# power.net
KiCad netlist of a schematic drawn in Altium Designer
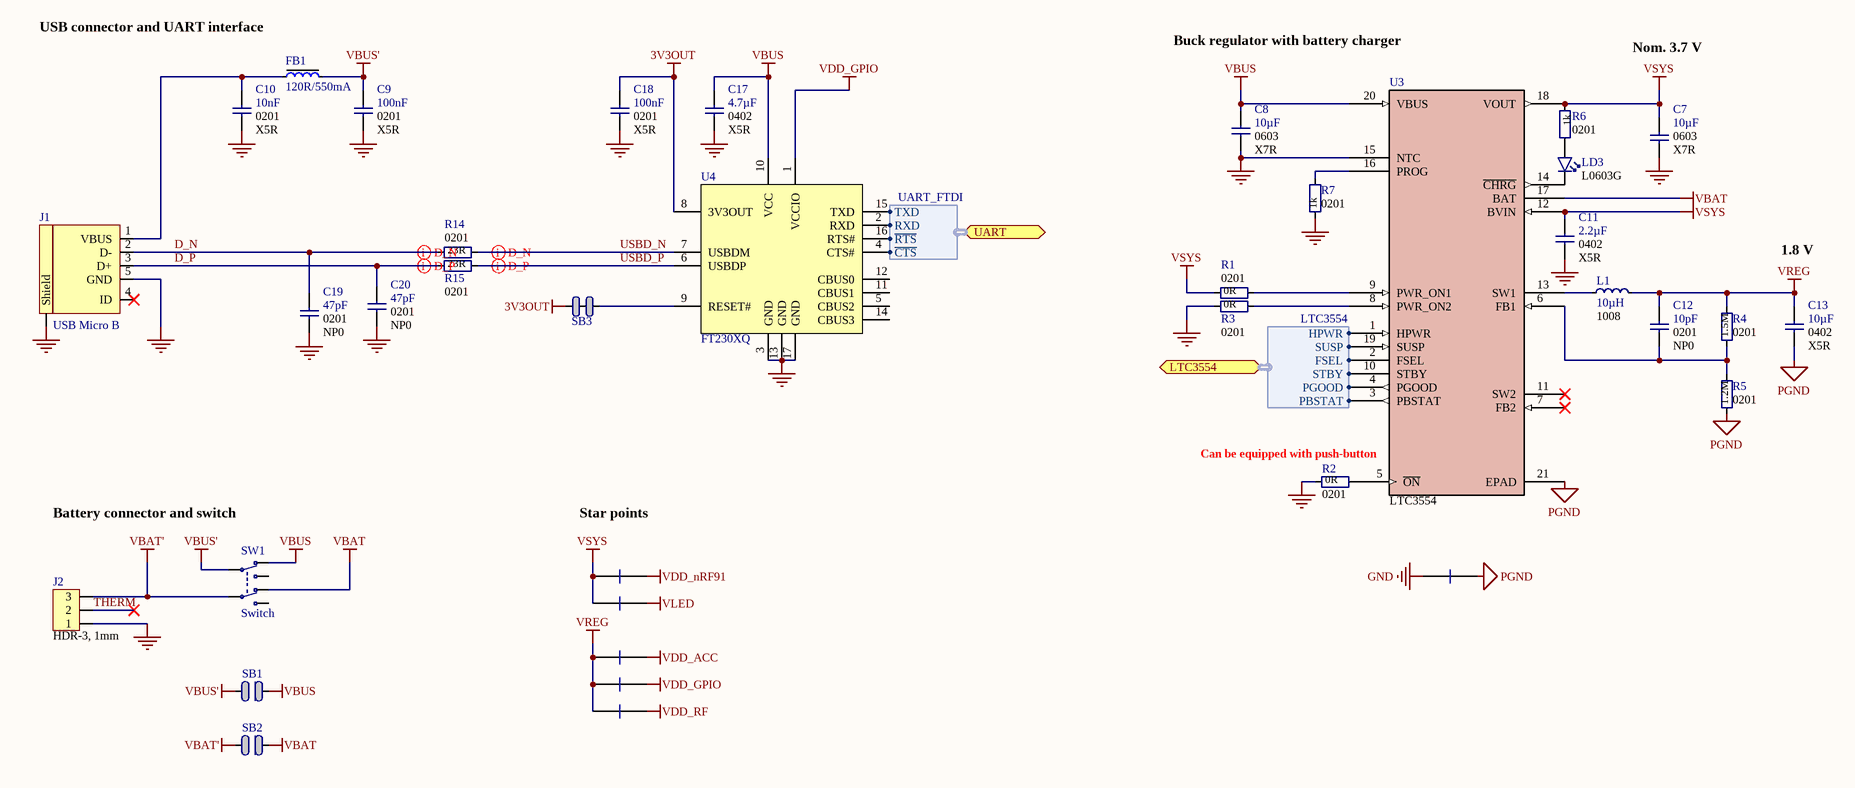
[diagram p0: _power.SchDoc]

(export (version "E")
  (design (tool "Eeschema 10.0.6"))
  (components
    (comp (ref "C7")
      (value "10µF")
      (footprint "CAPC1608X06L")
      (description "Capacitor, X7R, ±10%")
      (fields
        (field (name "FOOTPRINT DOC") "0603")
        (field (name "TEMPCOEFF") "X7R")
        (field (name "PUBLISHER") "Nordic Semiconductor")
      )
      (libsource (lib "_components") (part "CAP{colon}0603"))
    )
    (comp (ref "C8")
      (value "10µF")
      (footprint "CAPC1608X06L")
      (description "Capacitor, X7R, ±10%")
      (fields
        (field (name "FOOTPRINT DOC") "0603")
        (field (name "TEMPCOEFF") "X7R")
        (field (name "PUBLISHER") "Nordic Semiconductor")
      )
      (libsource (lib "_components") (part "CAP{colon}0603"))
    )
    (comp (ref "C9")
      (value "100nF")
      (footprint "CAPC0603X03L_C")
      (description "Capacitor, X5R, ±10%, 10V")
      (fields
        (field (name "FOOTPRINT DOC") "0201")
        (field (name "TEMPCOEFF") "X5R")
        (field (name "PUBLISHER") "Nordic Semiconductor")
      )
      (libsource (lib "_components") (part "CAP{colon}0201"))
    )
    (comp (ref "C10")
      (value "10nF")
      (footprint "CAPC0603X03L_C")
      (description "Capacitor, X5R, ±10%, 10V")
      (fields
        (field (name "FOOTPRINT DOC") "0201")
        (field (name "TEMPCOEFF") "X5R")
        (field (name "PUBLISHER") "Nordic Semiconductor")
      )
      (libsource (lib "_components") (part "CAP{colon}0201"))
    )
    (comp (ref "C11")
      (value "2.2µF")
      (footprint "CAPC1005X04L")
      (description "Capacitor, X5R, ±10%, 16V")
      (fields
        (field (name "FOOTPRINT DOC") "0402")
        (field (name "TEMPCOEFF") "X5R")
        (field (name "PUBLISHER") "Nordic Semiconductor")
      )
      (libsource (lib "_components") (part "CAP{colon}0402"))
    )
    (comp (ref "C12")
      (value "10pF")
      (footprint "CAPC0603X03L_C")
      (description "Capacitor, NP0")
      (fields
        (field (name "FOOTPRINT DOC") "0201")
        (field (name "TEMPCOEFF") "NP0")
        (field (name "PUBLISHER") "Nordic Semiconductor")
      )
      (libsource (lib "_components") (part "CAP{colon}0201"))
    )
    (comp (ref "C13")
      (value "10µF")
      (footprint "CAPC1005X04L")
      (description "Capacitor, X5R, ±20%")
      (fields
        (field (name "FOOTPRINT DOC") "0402")
        (field (name "TEMPCOEFF") "X5R")
        (field (name "PUBLISHER") "Nordic Semiconductor")
      )
      (libsource (lib "_components") (part "CAP{colon}0402"))
    )
    (comp (ref "C17")
      (value "4.7µF")
      (footprint "CAPC1005X04L")
      (description "Capacitor, X5R, ±10%, 16V")
      (fields
        (field (name "FOOTPRINT DOC") "0402")
        (field (name "TEMPCOEFF") "X5R")
        (field (name "PUBLISHER") "Nordic Semiconductor")
      )
      (libsource (lib "_components") (part "CAP{colon}0402"))
    )
    (comp (ref "C18")
      (value "100nF")
      (footprint "CAPC0603X03L_C")
      (description "Capacitor, X5R, ±10%, 10V")
      (fields
        (field (name "FOOTPRINT DOC") "0201")
        (field (name "TEMPCOEFF") "X5R")
        (field (name "PUBLISHER") "Nordic Semiconductor")
      )
      (libsource (lib "_components") (part "CAP{colon}0201"))
    )
    (comp (ref "C19")
      (value "47pF")
      (footprint "CAPC0603X03L_C")
      (description "Capacitor, NP0")
      (fields
        (field (name "FOOTPRINT DOC") "0201")
        (field (name "TEMPCOEFF") "NP0")
        (field (name "PUBLISHER") "Nordic Semiconductor")
      )
      (libsource (lib "_components") (part "CAP{colon}0201"))
    )
    (comp (ref "C20")
      (value "47pF")
      (footprint "CAPC0603X03L_C")
      (description "Capacitor, NP0")
      (fields
        (field (name "FOOTPRINT DOC") "0201")
        (field (name "TEMPCOEFF") "NP0")
        (field (name "PUBLISHER") "Nordic Semiconductor")
      )
      (libsource (lib "_components") (part "CAP{colon}0201"))
    )
    (comp (ref "FB1")
      (value "120R/550mA")
      (footprint "INDC1005X04L")
      (description "Ferrite Bead, 120 Ohm @ 100MHz, 500mA, 250 mOhm Max")
      (fields
        (field (name "PART NUMBER") "FB0805-120R@100M-550mA")
        (field (name "MANUFACTURER") "Murata")
        (field (name "PUBLISHER") "Nordic Semiconductor")
      )
      (libsource (lib "_components") (part "FB0402-120R@100M-500mA"))
    )
    (comp (ref "J1")
      (value "USB Micro B")
      (footprint "USB-Micro-B-RA-SMD-PiP")
      (description "MicroUSB-B-SMT")
      (fields
        (field (name "PART NUMBER") "USB-Micro-B-RA-SMD-PiP")
        (field (name "MANUFACTURER") "Amphenol ICC (FCI)")
        (field (name "PUBLISHER") "Nordic Semiconductor")
      )
      (libsource (lib "_components") (part "MiniUSB-AB-SMT"))
    )
    (comp (ref "J2")
      (value "HDR-3, 1mm")
      (footprint "SM03B-SRSS-TB")
      (description "1.0mm pitch connector side entry SMD")
      (fields
        (field (name "PART NUMBER") "SM03B-SRSS-TB")
        (field (name "MANUFACTURER") "JST")
        (field (name "PUBLISHER") "Nordic Semiconductor")
      )
      (libsource (lib "_components") (part "CONN-3"))
    )
    (comp (ref "L1")
      (value "10µH")
      (footprint "IND1008")
      (description "Switching regulator chip inductor, 2-Leads, Body 2.5x2.0x1.1 mm")
      (fields
        (field (name "MANUFACTURER") "Wurth Electronics Inc.")
        (field (name "MANUFACTURER PART NUMBER") "74479787247")
        (field (name "FOOTPRINT DOC") "1008")
        (field (name "PUBLISHER") "Nordic Semiconductor")
      )
      (libsource (lib "_components") (part "IND{colon}1008_REG"))
    )
    (comp (ref "LD3")
      (value "L0603G")
      (footprint "LED_0603_G")
      (description "LED, Green, 0603, 570nm, Vf=1.7V, 2.24..5.6mcd, - 40 to +100°C")
      (fields
        (field (name "PART NUMBER") "LG L29K Smartled Green")
        (field (name "MANUFACTURER") "Osram")
        (field (name "PUBLISHER") "Nordic Semiconductor")
      )
      (libsource (lib "_components") (part "D{colon}LED"))
    )
    (comp (ref "NT1")
      (value "Star point")
      (footprint "Net_tie_GND")
      (libsource (lib "_components") (part "NT{colon}Trace"))
    )
    (comp (ref "NT2")
      (value "Star point")
      (footprint "Net_tie_trace")
      (libsource (lib "_components") (part "NT{colon}Trace"))
    )
    (comp (ref "NT3")
      (value "Star point")
      (footprint "Net_tie_trace")
      (libsource (lib "_components") (part "NT{colon}Trace"))
    )
    (comp (ref "NT4")
      (value "Star point")
      (footprint "Net_tie_trace")
      (libsource (lib "_components") (part "NT{colon}Trace"))
    )
    (comp (ref "NT5")
      (value "Star point")
      (footprint "Net_tie_trace")
      (libsource (lib "_components") (part "NT{colon}Trace"))
    )
    (comp (ref "NT6")
      (value "Star point")
      (footprint "Net_tie_trace")
      (libsource (lib "_components") (part "NT{colon}Trace"))
    )
    (comp (ref "R1")
      (value "0R")
      (footprint "RESC0603X03L_C")
      (fields (field (name "FOOTPRINT DOC") "0201") (field (name "PUBLISHER") "Nordic Semiconductor"))
      (libsource (lib "") (part "RES{colon}0201_2"))
    )
    (comp (ref "R2")
      (value "0R")
      (footprint "RESC0603X03L_C")
      (fields (field (name "FOOTPRINT DOC") "0201") (field (name "PUBLISHER") "Nordic Semiconductor"))
      (libsource (lib "") (part "RES{colon}0201_2"))
    )
    (comp (ref "R3")
      (value "0R")
      (footprint "RESC0603X03L_C")
      (fields (field (name "FOOTPRINT DOC") "0201") (field (name "PUBLISHER") "Nordic Semiconductor"))
      (libsource (lib "") (part "RES{colon}0201_2"))
    )
    (comp (ref "R4")
      (value "1.5M")
      (footprint "RESC0603X03L_C")
      (fields (field (name "FOOTPRINT DOC") "0201") (field (name "PUBLISHER") "Nordic Semiconductor"))
      (libsource (lib "") (part "RES{colon}0201_1"))
    )
    (comp (ref "R5")
      (value "1.2M")
      (footprint "RESC0603X03L_C")
      (fields (field (name "FOOTPRINT DOC") "0201") (field (name "PUBLISHER") "Nordic Semiconductor"))
      (libsource (lib "") (part "RES{colon}0201_1"))
    )
    (comp (ref "R6")
      (value "1k")
      (footprint "RESC0603X03L_C")
      (fields (field (name "FOOTPRINT DOC") "0201") (field (name "PUBLISHER") "Nordic Semiconductor"))
      (libsource (lib "_components") (part "RES{colon}0201"))
    )
    (comp (ref "R7")
      (value "1k")
      (footprint "RESC0603X03L_C")
      (fields (field (name "FOOTPRINT DOC") "0201") (field (name "PUBLISHER") "Nordic Semiconductor"))
      (libsource (lib "") (part "RES{colon}0201_1"))
    )
    (comp (ref "R14")
      (value "23R")
      (footprint "RESC0603X03L_C")
      (fields (field (name "FOOTPRINT DOC") "0201") (field (name "PUBLISHER") "Nordic Semiconductor"))
      (libsource (lib "") (part "RES{colon}0201_2"))
    )
    (comp (ref "R15")
      (value "23R")
      (footprint "RESC0603X03L_C")
      (fields (field (name "FOOTPRINT DOC") "0201") (field (name "PUBLISHER") "Nordic Semiconductor"))
      (libsource (lib "") (part "RES{colon}0201_2"))
    )
    (comp (ref "SB1")
      (value "Solderbridge")
      (footprint "Solderbridge")
      (fields (field (name "PUBLISHER") "Nordic Semiconductor"))
      (libsource (lib "_components") (part "SOLDERBRIDGE"))
    )
    (comp (ref "SB2")
      (value "Solderbridge")
      (footprint "Solderbridge")
      (fields (field (name "PUBLISHER") "Nordic Semiconductor"))
      (libsource (lib "_components") (part "SOLDERBRIDGE"))
    )
    (comp (ref "SB3")
      (value "Solderbridge")
      (footprint "Solderbridge_Shorted")
      (description "Shorted Solderbridge")
      (fields (field (name "PUBLISHER") "Nordic Semiconductor"))
      (libsource (lib "_components") (part "SOLDERBRIDGE_SHORTED"))
    )
    (comp (ref "SW1")
      (value "Switch")
      (footprint "Switch-Slide-RA-J-Lead-DPDT-8.5x3.5mm")
      (description "SMD slide Switch (ON-ON)")
      (fields
        (field (name "PART NUMBER") "Switch-Slide-RA-J-Lead-DPDT-8.5x3.5mm_Copal")
        (field (name "MANUFACTURER") "Copal Electronics Inc")
        (field (name "PUBLISHER") "Nordic Semiconductor")
      )
      (libsource (lib "_components") (part "SW-DPDT"))
    )
    (comp (ref "U3")
      (value "LTC3554")
      (footprint "QFN40P300X300X80_HS-21N")
      (description "IC USB POWER MANAGER 20UTQFN")
      (fields
        (field (name "MANUFACTURER_PART_NUMBER") "LTC3554EUD-3#PBF")
        (field (name "COPYRIGHT") "Nordic Semiconductor")
      )
      (libsource (lib "_components") (part "LTC3554EUD-3#PBF"))
    )
    (comp (ref "U4")
      (value "FT230XQ")
      (footprint "QFN65P400X400X80_HS-17N")
      (description "USB Bridge, USB to UART USB 2.0 UART Interface 16-QFN (4x4)")
      (fields (field (name "MANUFACTURER") "FTDI") (field (name "PUBLISHER") "Nordic Semiconductor"))
      (libsource (lib "_components") (part "FT230X"))
    )
  )
  (nets
    (net (code "3") (name "/D_N") (class "Default")
      (node (ref "C19") (pin "2") (pinfunction "2_2") (pintype "passive"))
      (node (ref "J1") (pin "2") (pinfunction "D-_2") (pintype "passive"))
      (node (ref "R14") (pin "1") (pinfunction "1_1") (pintype "passive"))
    )
    (net (code "4") (name "/D_P") (class "Default")
      (node (ref "C20") (pin "1") (pinfunction "1_1") (pintype "passive"))
      (node (ref "J1") (pin "3") (pinfunction "D+_3") (pintype "passive"))
      (node (ref "R15") (pin "1") (pinfunction "1_1") (pintype "passive"))
    )
    (net (code "5") (name "/FSEL") (class "Default")
      (node (ref "U3") (pin "2") (pinfunction "FSEL_2") (pintype "passive"))
    )
    (net (code "6") (name "/HPWR") (class "Default")
      (node (ref "U3") (pin "1") (pinfunction "HPWR_1") (pintype "input"))
    )
    (net (code "7") (name "/PBSTAT") (class "Default")
      (node (ref "U3") (pin "3") (pinfunction "PBSTAT_3") (pintype "output"))
    )
    (net (code "8") (name "/PGOOD") (class "Default")
      (node (ref "U3") (pin "4") (pinfunction "PGOOD_4") (pintype "output"))
    )
    (net (code "9") (name "/RXD") (class "Default")
      (node (ref "U4") (pin "2") (pinfunction "RXD_2") (pintype "passive"))
    )
    (net (code "10") (name "/STBY") (class "Default")
      (node (ref "U3") (pin "10") (pinfunction "STBY_10") (pintype "passive"))
    )
    (net (code "11") (name "/SUSP") (class "Default")
      (node (ref "U3") (pin "19") (pinfunction "SUSP_19") (pintype "input"))
    )
    (net (code "12") (name "/THERM") (class "Default")
      (node (ref "J2") (pin "2") (pinfunction "2_2") (pintype "passive+no_connect"))
    )
    (net (code "13") (name "/TXD") (class "Default")
      (node (ref "U4") (pin "15") (pinfunction "TXD_15") (pintype "passive"))
    )
    (net (code "14") (name "/USBD_N") (class "Default")
      (node (ref "R14") (pin "2") (pinfunction "2_2") (pintype "passive"))
      (node (ref "U4") (pin "7") (pinfunction "USBDM_7") (pintype "passive"))
    )
    (net (code "15") (name "/USBD_P") (class "Default")
      (node (ref "R15") (pin "2") (pinfunction "2_2") (pintype "passive"))
      (node (ref "U4") (pin "6") (pinfunction "USBDP_6") (pintype "passive"))
    )
    (net (code "18") (name "/~{CTS}") (class "Default")
      (node (ref "U4") (pin "4") (pinfunction "CTS#_4") (pintype "passive"))
    )
    (net (code "19") (name "/~{RTS}") (class "Default")
      (node (ref "U4") (pin "16") (pinfunction "RTS#_16") (pintype "power_in"))
    )
    (net (code "20") (name "3V3OUT") (class "Default")
      (node (ref "C18") (pin "1") (pinfunction "1_1") (pintype "passive"))
      (node (ref "SB3") (pin "2") (pinfunction "1_2") (pintype "passive"))
      (node (ref "U4") (pin "8") (pinfunction "3V3OUT_8") (pintype "passive"))
    )
    (net (code "21") (name "GND") (class "Default")
      (node (ref "C10") (pin "2") (pinfunction "2_2") (pintype "passive"))
      (node (ref "C11") (pin "2") (pinfunction "2_2") (pintype "passive"))
      (node (ref "C17") (pin "2") (pinfunction "2_2") (pintype "passive"))
      (node (ref "C18") (pin "2") (pinfunction "2_2") (pintype "passive"))
      (node (ref "C19") (pin "1") (pinfunction "1_1") (pintype "passive"))
      (node (ref "C20") (pin "2") (pinfunction "2_2") (pintype "passive"))
      (node (ref "C7") (pin "2") (pinfunction "2_2") (pintype "passive"))
      (node (ref "C8") (pin "2") (pinfunction "2_2") (pintype "passive"))
      (node (ref "C9") (pin "2") (pinfunction "2_2") (pintype "passive"))
      (node (ref "J1") (pin "5") (pinfunction "GND_5") (pintype "power_in"))
      (node (ref "J1") (pin "6") (pinfunction "Shield_6") (pintype "power_in"))
      (node (ref "J2") (pin "1") (pinfunction "1_1") (pintype "passive"))
      (node (ref "NT1") (pin "1") (pinfunction "1_1") (pintype "passive"))
      (node (ref "R2") (pin "1") (pinfunction "1_1") (pintype "passive"))
      (node (ref "R3") (pin "1") (pinfunction "1_1") (pintype "passive"))
      (node (ref "R7") (pin "1") (pinfunction "1_1") (pintype "passive"))
      (node (ref "U3") (pin "15") (pinfunction "NTC_15") (pintype "passive"))
      (node (ref "U4") (pin "13") (pinfunction "GND_13") (pintype "power_in"))
      (node (ref "U4") (pin "17") (pinfunction "GND_17") (pintype "power_in"))
      (node (ref "U4") (pin "3") (pinfunction "GND_3") (pintype "passive"))
    )
    (net (code "22") (name "Net-(J1-VBUS)") (class "Default")
      (node (ref "C10") (pin "1") (pinfunction "1_1") (pintype "passive"))
      (node (ref "FB1") (pin "1") (pinfunction "1_1") (pintype "passive"))
      (node (ref "J1") (pin "1") (pinfunction "VBUS_1") (pintype "power_in"))
    )
    (net (code "23") (name "Net-(LD3-A)") (class "Default")
      (node (ref "LD3") (pin "2") (pinfunction "A_2") (pintype "passive"))
      (node (ref "R6") (pin "2") (pinfunction "2_2") (pintype "passive"))
    )
    (net (code "24") (name "Net-(LD3-C)") (class "Default")
      (node (ref "LD3") (pin "1") (pinfunction "C_1") (pintype "passive"))
      (node (ref "U3") (pin "14") (pinfunction "~{CHRG}_14") (pintype "output"))
    )
    (net (code "25") (name "Net-(SB3-0)") (class "Default")
      (node (ref "SB3") (pin "1") (pinfunction "0_1") (pintype "passive"))
      (node (ref "U4") (pin "9") (pinfunction "RESET#_9") (pintype "passive"))
    )
    (net (code "26") (name "Net-(U3-FB1)") (class "Default")
      (node (ref "C12") (pin "2") (pinfunction "2_2") (pintype "passive"))
      (node (ref "R4") (pin "1") (pinfunction "1_1") (pintype "passive"))
      (node (ref "R5") (pin "2") (pinfunction "2_2") (pintype "passive"))
      (node (ref "U3") (pin "6") (pinfunction "FB1_6") (pintype "input"))
    )
    (net (code "27") (name "Net-(U3-PROG)") (class "Default")
      (node (ref "R7") (pin "2") (pinfunction "2_2") (pintype "passive"))
      (node (ref "U3") (pin "16") (pinfunction "PROG_16") (pintype "passive"))
    )
    (net (code "28") (name "Net-(U3-PWR_ON1)") (class "Default")
      (node (ref "R1") (pin "2") (pinfunction "2_2") (pintype "passive"))
      (node (ref "U3") (pin "9") (pinfunction "PWR_ON1_9") (pintype "input"))
    )
    (net (code "29") (name "Net-(U3-PWR_ON2)") (class "Default")
      (node (ref "R3") (pin "2") (pinfunction "2_2") (pintype "passive"))
      (node (ref "U3") (pin "8") (pinfunction "PWR_ON2_8") (pintype "input"))
    )
    (net (code "30") (name "Net-(U3-SW1)") (class "Default")
      (node (ref "L1") (pin "1") (pinfunction "1_1") (pintype "passive"))
      (node (ref "U3") (pin "13") (pinfunction "SW1_13") (pintype "passive"))
    )
    (net (code "31") (name "Net-(U3-~{ON})") (class "Default")
      (node (ref "R2") (pin "2") (pinfunction "2_2") (pintype "passive"))
      (node (ref "U3") (pin "5") (pinfunction "~{ON}_5") (pintype "input"))
    )
    (net (code "32") (name "PGND") (class "Default")
      (node (ref "C13") (pin "2") (pinfunction "2_2") (pintype "passive"))
      (node (ref "NT1") (pin "2") (pinfunction "2_2") (pintype "passive"))
      (node (ref "R5") (pin "1") (pinfunction "1_1") (pintype "passive"))
      (node (ref "U3") (pin "21") (pinfunction "EPAD_21") (pintype "passive"))
    )
    (net (code "33") (name "VBAT") (class "Default")
      (node (ref "SB2") (pin "2") (pinfunction "1_2") (pintype "passive"))
      (node (ref "SW1") (pin "6") (pinfunction "N.C-2_6") (pintype "passive"))
      (node (ref "U3") (pin "17") (pinfunction "BAT_17") (pintype "passive"))
    )
    (net (code "34") (name "VBAT'") (class "Default")
      (node (ref "J2") (pin "3") (pinfunction "3_3") (pintype "passive"))
      (node (ref "SB2") (pin "1") (pinfunction "0_1") (pintype "passive"))
      (node (ref "SW1") (pin "5") (pinfunction "COM-2_5") (pintype "passive"))
    )
    (net (code "35") (name "VBUS") (class "Default")
      (node (ref "C17") (pin "1") (pinfunction "1_1") (pintype "passive"))
      (node (ref "C8") (pin "1") (pinfunction "1_1") (pintype "passive"))
      (node (ref "SB1") (pin "2") (pinfunction "1_2") (pintype "passive"))
      (node (ref "SW1") (pin "3") (pinfunction "N.C-1_3") (pintype "passive"))
      (node (ref "U3") (pin "20") (pinfunction "VBUS_20") (pintype "input"))
      (node (ref "U4") (pin "10") (pinfunction "VCC_10") (pintype "passive"))
    )
    (net (code "36") (name "VBUS'") (class "Default")
      (node (ref "C9") (pin "1") (pinfunction "1_1") (pintype "passive"))
      (node (ref "FB1") (pin "2") (pinfunction "2_2") (pintype "passive"))
      (node (ref "SB1") (pin "1") (pinfunction "0_1") (pintype "passive"))
      (node (ref "SW1") (pin "2") (pinfunction "COM-1_2") (pintype "passive"))
    )
    (net (code "37") (name "VDD_ACC") (class "Default")
      (node (ref "NT4") (pin "2") (pinfunction "2_2") (pintype "passive"))
    )
    (net (code "38") (name "VDD_GPIO") (class "Default")
      (node (ref "NT5") (pin "2") (pinfunction "2_2") (pintype "passive"))
      (node (ref "U4") (pin "1") (pinfunction "VCCIO_1") (pintype "power_in"))
    )
    (net (code "39") (name "VDD_RF") (class "Default")
      (node (ref "NT6") (pin "2") (pinfunction "2_2") (pintype "passive"))
    )
    (net (code "40") (name "VDD_nRF91") (class "Default")
      (node (ref "NT2") (pin "2") (pinfunction "2_2") (pintype "passive"))
    )
    (net (code "41") (name "VLED") (class "Default")
      (node (ref "NT3") (pin "2") (pinfunction "2_2") (pintype "passive"))
    )
    (net (code "42") (name "VREG") (class "Default")
      (node (ref "C12") (pin "1") (pinfunction "1_1") (pintype "passive"))
      (node (ref "C13") (pin "1") (pinfunction "1_1") (pintype "passive"))
      (node (ref "L1") (pin "2") (pinfunction "2_2") (pintype "passive"))
      (node (ref "NT4") (pin "1") (pinfunction "1_1") (pintype "passive"))
      (node (ref "NT5") (pin "1") (pinfunction "1_1") (pintype "passive"))
      (node (ref "NT6") (pin "1") (pinfunction "1_1") (pintype "passive"))
      (node (ref "R4") (pin "2") (pinfunction "2_2") (pintype "passive"))
    )
    (net (code "43") (name "VSYS") (class "Default")
      (node (ref "C11") (pin "1") (pinfunction "1_1") (pintype "passive"))
      (node (ref "C7") (pin "1") (pinfunction "1_1") (pintype "passive"))
      (node (ref "NT2") (pin "1") (pinfunction "1_1") (pintype "passive"))
      (node (ref "NT3") (pin "1") (pinfunction "1_1") (pintype "passive"))
      (node (ref "R1") (pin "1") (pinfunction "1_1") (pintype "passive"))
      (node (ref "R6") (pin "1") (pinfunction "1_1") (pintype "passive"))
      (node (ref "U3") (pin "12") (pinfunction "BVIN_12") (pintype "input"))
      (node (ref "U3") (pin "18") (pinfunction "VOUT_18") (pintype "output"))
    )
    (net (code "44") (name "unconnected-(J1-ID-Pad4)") (class "Default")
      (node (ref "J1") (pin "4") (pinfunction "ID_4") (pintype "passive+no_connect"))
    )
    (net (code "45") (name "unconnected-(SW1-N.O-1-Pad1)") (class "Default")
      (node (ref "SW1") (pin "1") (pinfunction "N.O-1_1") (pintype "passive"))
    )
    (net (code "46") (name "unconnected-(SW1-N.O-2-Pad4)") (class "Default")
      (node (ref "SW1") (pin "4") (pinfunction "N.O-2_4") (pintype "passive"))
    )
    (net (code "47") (name "unconnected-(U3-FB2-Pad7)") (class "Default")
      (node (ref "U3") (pin "7") (pinfunction "FB2_7") (pintype "input+no_connect"))
    )
    (net (code "48") (name "unconnected-(U3-SW2-Pad11)") (class "Default")
      (node (ref "U3") (pin "11") (pinfunction "SW2_11") (pintype "passive+no_connect"))
    )
    (net (code "49") (name "unconnected-(U4-CBUS0-Pad12)") (class "Default")
      (node (ref "U4") (pin "12") (pinfunction "CBUS0_12") (pintype "power_in"))
    )
    (net (code "50") (name "unconnected-(U4-CBUS1-Pad11)") (class "Default")
      (node (ref "U4") (pin "11") (pinfunction "CBUS1_11") (pintype "passive"))
    )
    (net (code "51") (name "unconnected-(U4-CBUS2-Pad5)") (class "Default")
      (node (ref "U4") (pin "5") (pinfunction "CBUS2_5") (pintype "passive"))
    )
    (net (code "52") (name "unconnected-(U4-CBUS3-Pad14)") (class "Default")
      (node (ref "U4") (pin "14") (pinfunction "CBUS3_14") (pintype "power_in"))
    )
  )
)
